# driverpower.net
KiCad netlist of a schematic drawn in Altium Designer
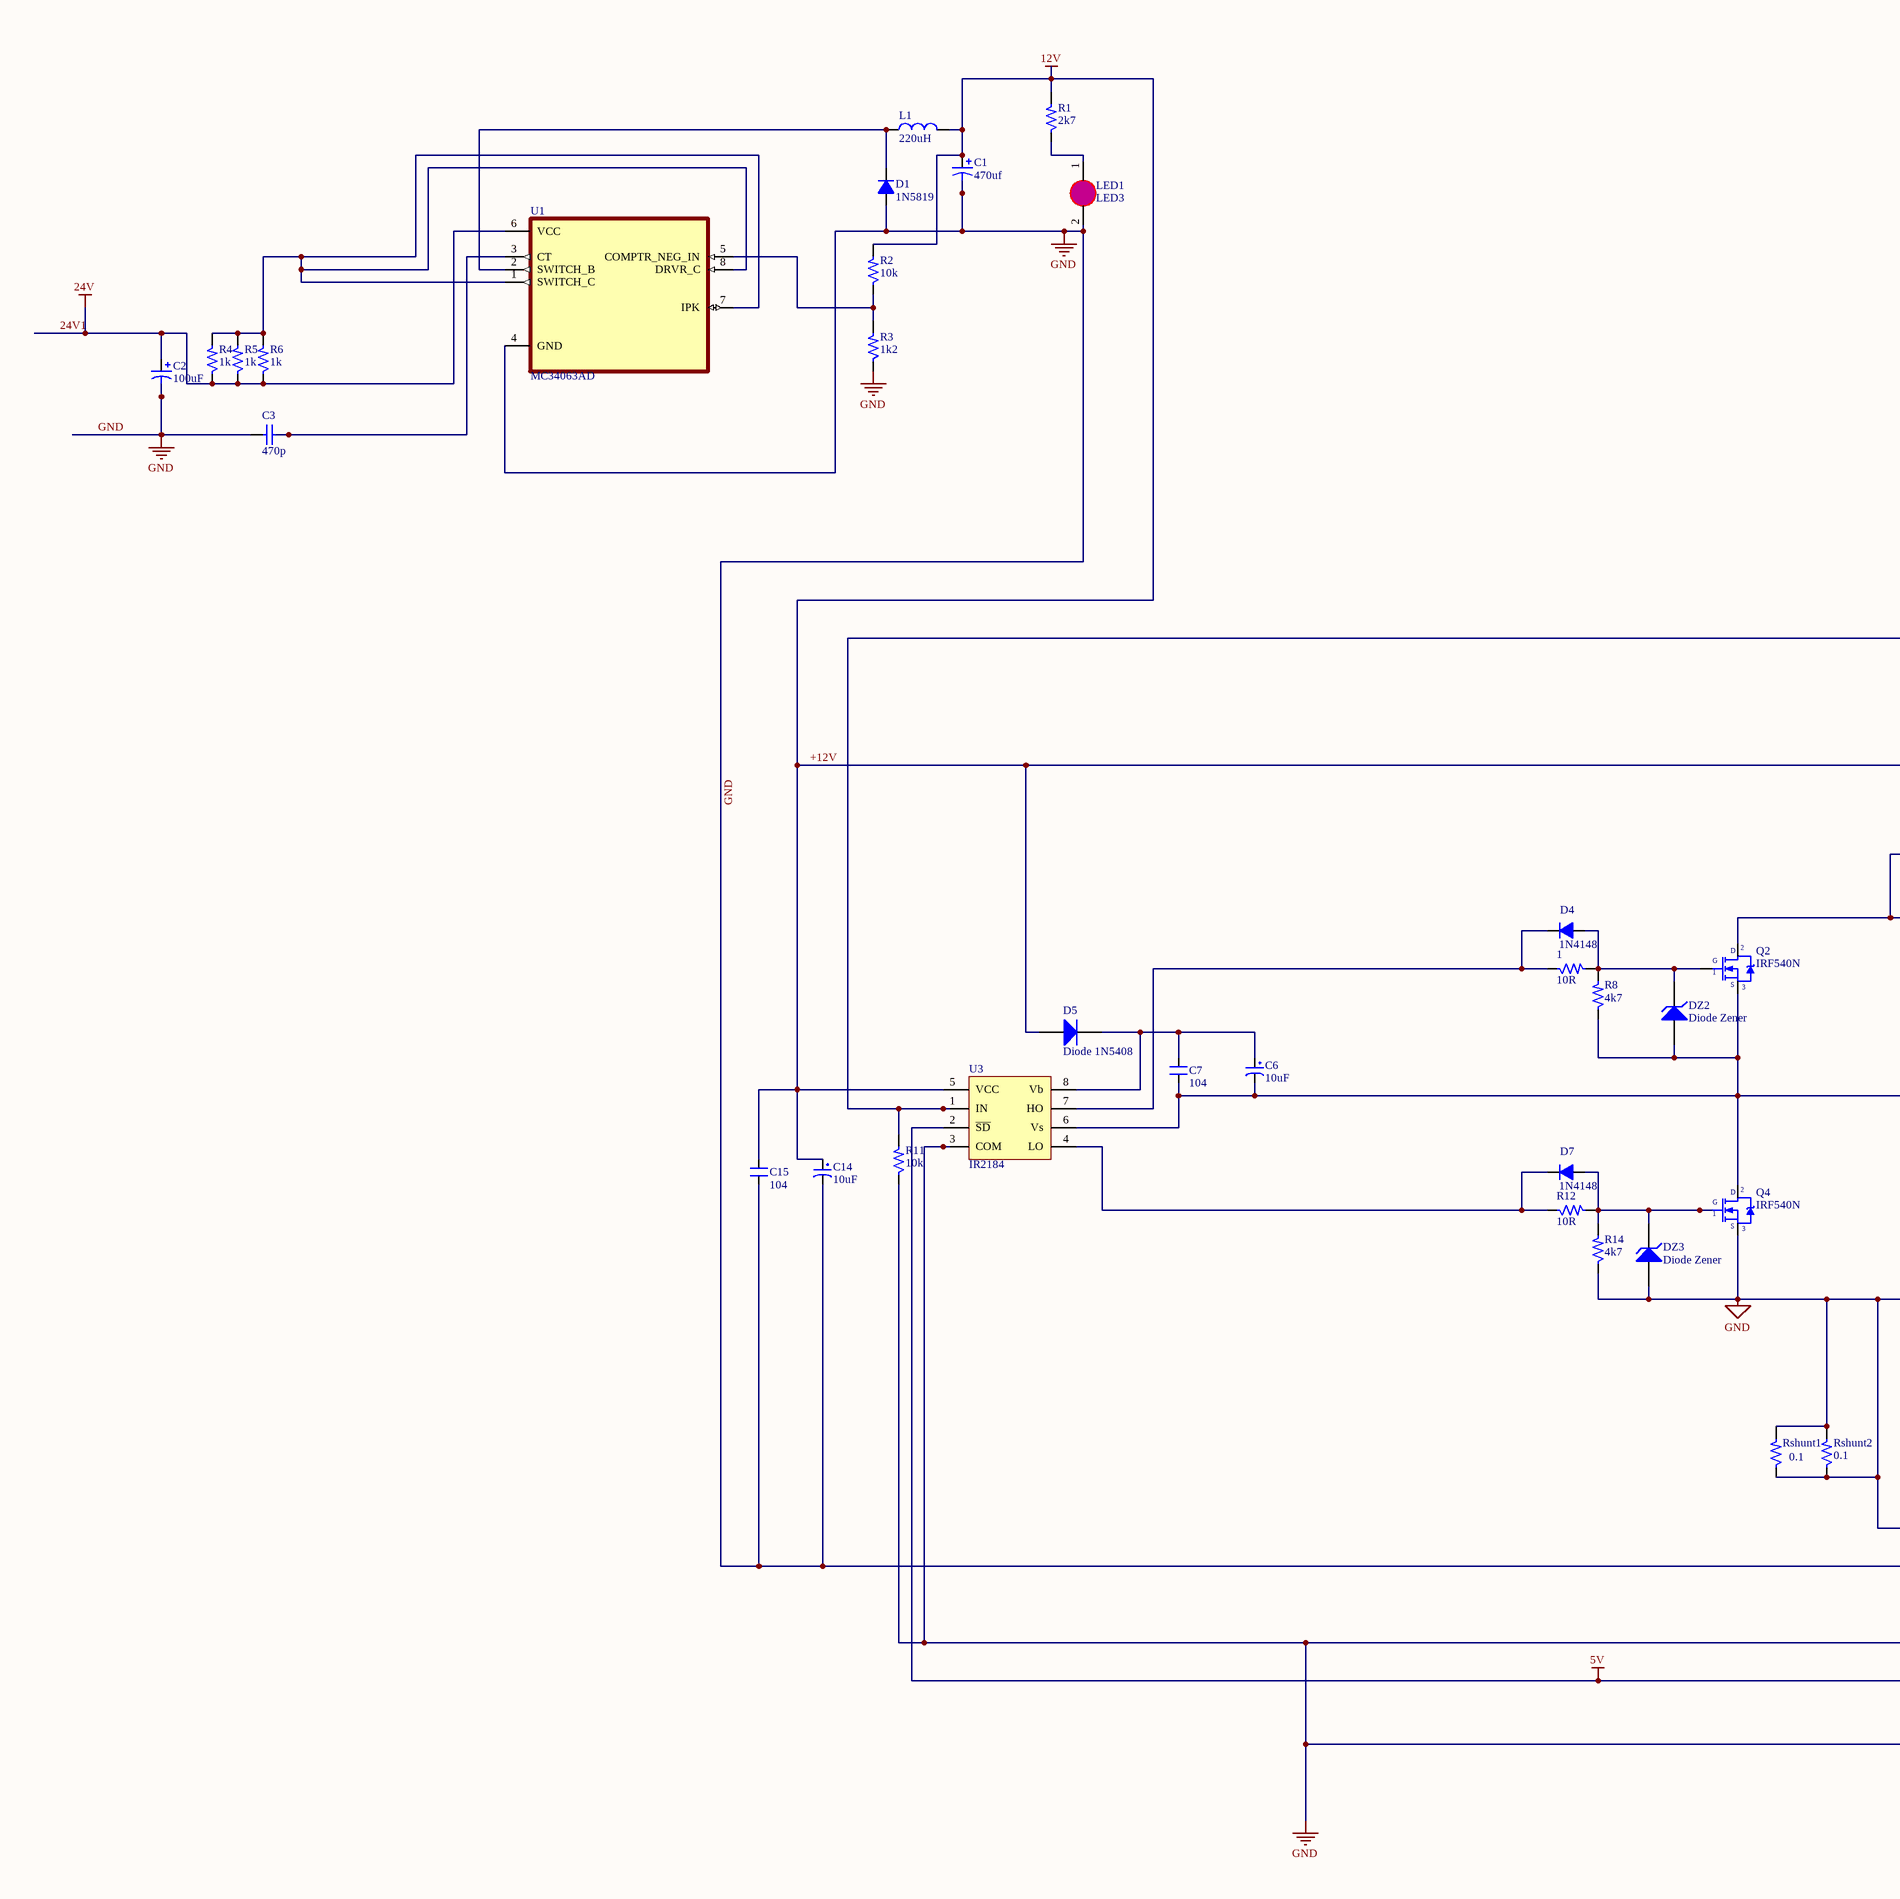
[diagram p0: driverpower.SchDoc, left]
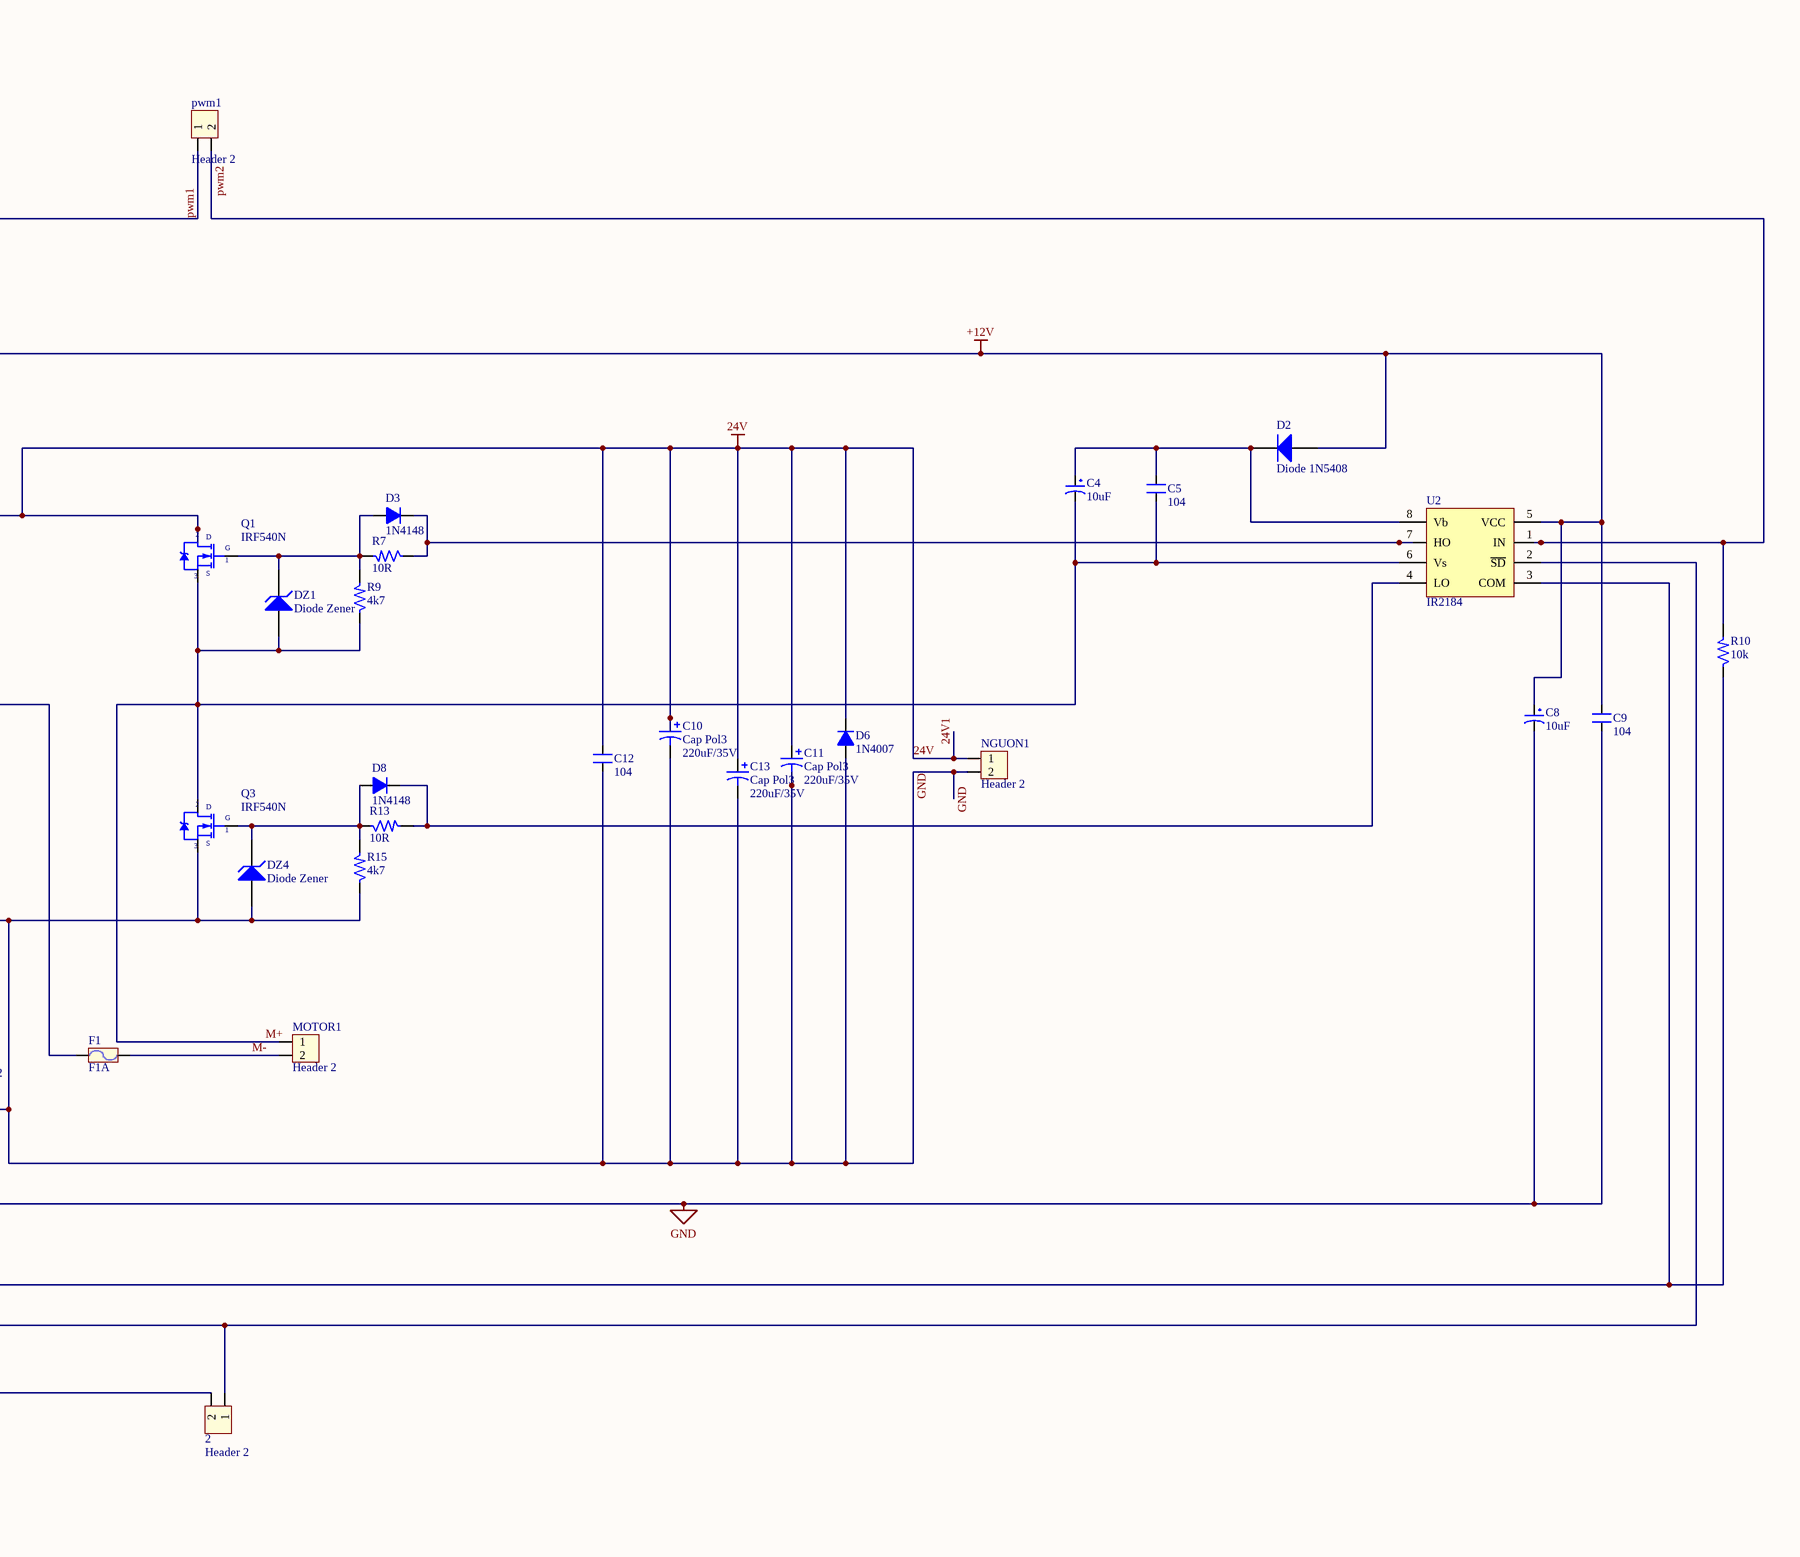
[diagram p1: driverpower.SchDoc, right]

(export (version "E")
  (design (tool "Eeschema 10.0.6"))
  (components
    (comp (ref "1")
      (value "10R")
      (footprint "SM-1206")
      (description "Resistor 1/4W")
      (libsource (lib "syhaunguyen") (part "R"))
    )
    (comp (ref "2")
      (value "Header 2")
      (footprint "HED2")
      (description "Header 2 (Green)")
      (libsource (lib "") (part "Hed2_1"))
    )
    (comp (ref "C1")
      (value "470uf")
      (footprint "C3MM")
      (description "Polarized Capacitor (Axial)")
      (fields (field (name "PUBLISHER") "Altium Limited"))
      (libsource (lib "Schematic") (part "Cap Pol 3mm"))
    )
    (comp (ref "C2")
      (value "100uF")
      (footprint "C3MM")
      (description "Polarized Capacitor (Axial)")
      (fields (field (name "PUBLISHER") "Altium Limited"))
      (libsource (lib "Schematic") (part "Cap Pol 3mm"))
    )
    (comp (ref "C3") (value "470p") (footprint "C1206") (libsource (lib "Schematic") (part "Cap SMD 1206")))
    (comp (ref "C4")
      (value "10uF")
      (footprint "CP1/2")
      (description "Cap P  0,1uF < 22uF , 16 - 50V")
      (libsource (lib "syhaunguyen") (part "CP1"))
    )
    (comp (ref "C5")
      (value "104")
      (footprint "SM-0805")
      (description "Cap SMD")
      (libsource (lib "My Library") (part "CM"))
    )
    (comp (ref "C6")
      (value "10uF")
      (footprint "CP1/2")
      (description "Cap P  0,1uF < 22uF , 16 - 50V")
      (libsource (lib "syhaunguyen") (part "CP1"))
    )
    (comp (ref "C7")
      (value "104")
      (footprint "SM-0805")
      (description "Cap SMD")
      (libsource (lib "My Library") (part "CM"))
    )
    (comp (ref "C8")
      (value "10uF")
      (footprint "CP1/2")
      (description "Cap P  0,1uF < 22uF , 16 - 50V")
      (libsource (lib "syhaunguyen") (part "CP1"))
    )
    (comp (ref "C9")
      (value "104")
      (footprint "SM-0805")
      (description "Cap SMD")
      (libsource (lib "My Library") (part "CM"))
    )
    (comp (ref "C10")
      (value "Cap Pol3")
      (footprint "CP2/5")
      (description "Polarized Capacitor (Surface Mount)")
      (fields (field (name "ALTIUM_VALUE") "220uF/35V") (field (name "PUBLISHER") "Altium Limited"))
      (libsource (lib "syhaunguyen") (part "Cap Pol3"))
    )
    (comp (ref "C11")
      (value "Cap Pol3")
      (footprint "CP2/5")
      (description "Polarized Capacitor (Surface Mount)")
      (fields (field (name "ALTIUM_VALUE") "220uF/35V") (field (name "PUBLISHER") "Altium Limited"))
      (libsource (lib "syhaunguyen") (part "Cap Pol3"))
    )
    (comp (ref "C12")
      (value "104")
      (footprint "SM-0805")
      (description "Cap SMD")
      (libsource (lib "My Library") (part "CM"))
    )
    (comp (ref "C13")
      (value "Cap Pol3")
      (footprint "CP2/5")
      (description "Polarized Capacitor (Surface Mount)")
      (fields (field (name "ALTIUM_VALUE") "220uF/35V") (field (name "PUBLISHER") "Altium Limited"))
      (libsource (lib "syhaunguyen") (part "Cap Pol3"))
    )
    (comp (ref "C14")
      (value "10uF")
      (footprint "CP1/2")
      (description "Cap P  0,1uF < 22uF , 16 - 50V")
      (libsource (lib "syhaunguyen") (part "CP1"))
    )
    (comp (ref "C15")
      (value "104")
      (footprint "SM-0805")
      (description "Cap SMD")
      (libsource (lib "My Library") (part "CM"))
    )
    (comp (ref "D1")
      (value "1N5819")
      (footprint "D5A")
      (description "Diode 5A")
      (libsource (lib "syhaunguyen") (part "D5A"))
    )
    (comp (ref "D2")
      (value "Diode 1N5408")
      (footprint "DO-201AD")
      (description "3 Amp Medium Power Silicon Rectifier Diode")
      (fields (field (name "PUBLISHER") "Altium Limited"))
      (libsource (lib "Miscellaneous Devices") (part "Diode 1N5408"))
    )
    (comp (ref "D3")
      (value "1N4148")
      (footprint "D1A")
      (description "Diode 1A")
      (libsource (lib "syhaunguyen") (part "D1A"))
    )
    (comp (ref "D4")
      (value "1N4148")
      (footprint "D1A")
      (description "Diode 1A")
      (libsource (lib "syhaunguyen") (part "D1A"))
    )
    (comp (ref "D5")
      (value "Diode 1N5408")
      (footprint "DO-201AD")
      (description "3 Amp Medium Power Silicon Rectifier Diode")
      (fields (field (name "PUBLISHER") "Altium Limited"))
      (libsource (lib "Miscellaneous Devices") (part "Diode 1N5408"))
    )
    (comp (ref "D6")
      (value "1N4007")
      (footprint "D1A")
      (description "Diode 1A")
      (libsource (lib "My Library") (part "D1A"))
    )
    (comp (ref "D7")
      (value "1N4148")
      (footprint "D1A")
      (description "Diode 1A")
      (libsource (lib "syhaunguyen") (part "D1A"))
    )
    (comp (ref "D8")
      (value "1N4148")
      (footprint "D1A")
      (description "Diode 1A")
      (libsource (lib "syhaunguyen") (part "D1A"))
    )
    (comp (ref "DZ1")
      (value "Diode Zener")
      (footprint "DIODE/NOM/0.5A")
      (description "Zener Diode")
      (fields (field (name "PUBLISHER") "Altium Limited"))
      (libsource (lib "Schematic") (part "Diode Zener"))
    )
    (comp (ref "DZ2")
      (value "Diode Zener")
      (footprint "DIODE/NOM/0.5A")
      (description "Zener Diode")
      (fields (field (name "PUBLISHER") "Altium Limited"))
      (libsource (lib "Schematic") (part "Diode Zener"))
    )
    (comp (ref "DZ3")
      (value "Diode Zener")
      (footprint "DIODE/NOM/0.5A")
      (description "Zener Diode")
      (fields (field (name "PUBLISHER") "Altium Limited"))
      (libsource (lib "Schematic") (part "Diode Zener"))
    )
    (comp (ref "DZ4")
      (value "Diode Zener")
      (footprint "DIODE/NOM/0.5A")
      (description "Zener Diode")
      (fields (field (name "PUBLISHER") "Altium Limited"))
      (libsource (lib "Schematic") (part "Diode Zener"))
    )
    (comp (ref "F1")
      (value "F1A")
      (footprint "Fuse")
      (description "Fuse")
      (fields (field (name "DESIGNED BY") "VanDungEvn"))
      (libsource (lib "syhaunguyen") (part "Fuse"))
    )
    (comp (ref "L1")
      (value "220uH")
      (footprint "L/0.4")
      (description "Inductor")
      (libsource (lib "syhaunguyen") (part "L1"))
    )
    (comp (ref "LED1")
      (value "LED3")
      (footprint "LED0805")
      (description "LED 3mm")
      (libsource (lib "Schematic") (part "LEDSMD"))
    )
    (comp (ref "MOTOR1")
      (value "Header 2")
      (footprint "HED2")
      (description "Header 2 (Green)")
      (libsource (lib "My Library") (part "Hed2"))
    )
    (comp (ref "NGUON1")
      (value "Header 2")
      (footprint "HED2")
      (description "Header 2 (Green)")
      (libsource (lib "My Library") (part "Hed2"))
    )
    (comp (ref "pwm1")
      (value "Header 2")
      (footprint "HED2")
      (description "Header 2 (Green)")
      (libsource (lib "syhaunguyen") (part "Hed2"))
    )
    (comp (ref "Q1")
      (value "IRF540N")
      (footprint "QTO-220")
      (description "MOSFET N - CHANNEL 500V - 0.75 - 8A - TO-220")
      (libsource (lib "syhaunguyen") (part "IRF840"))
    )
    (comp (ref "Q2")
      (value "IRF540N")
      (footprint "QTO-220")
      (description "MOSFET N - CHANNEL 500V - 0.75 - 8A - TO-220")
      (libsource (lib "syhaunguyen") (part "IRF840"))
    )
    (comp (ref "Q3")
      (value "IRF540N")
      (footprint "QTO-220")
      (description "MOSFET N - CHANNEL 500V - 0.75 - 8A - TO-220")
      (libsource (lib "syhaunguyen") (part "IRF840"))
    )
    (comp (ref "Q4")
      (value "IRF540N")
      (footprint "QTO-220")
      (description "MOSFET N - CHANNEL 500V - 0.75 - 8A - TO-220")
      (libsource (lib "syhaunguyen") (part "IRF840"))
    )
    (comp (ref "R1")
      (value "2k7")
      (footprint "SM-1206")
      (description "Resistor 1/4W")
      (libsource (lib "syhaunguyen") (part "R"))
    )
    (comp (ref "R2")
      (value "10k")
      (footprint "SM-1206")
      (description "Resistor 1/4W")
      (libsource (lib "syhaunguyen") (part "R"))
    )
    (comp (ref "R3")
      (value "1k2")
      (footprint "SM-1206")
      (description "Resistor 1/4W")
      (libsource (lib "syhaunguyen") (part "R"))
    )
    (comp (ref "R4")
      (value "1k")
      (footprint "SM-1206")
      (description "Resistor 1/4W")
      (libsource (lib "syhaunguyen") (part "R"))
    )
    (comp (ref "R5")
      (value "1k")
      (footprint "SM-1206")
      (description "Resistor 1/4W")
      (libsource (lib "syhaunguyen") (part "R"))
    )
    (comp (ref "R6")
      (value "1k")
      (footprint "SM-1206")
      (description "Resistor 1/4W")
      (libsource (lib "syhaunguyen") (part "R"))
    )
    (comp (ref "R7")
      (value "10R")
      (footprint "SM-1206")
      (description "Resistor 1/4W")
      (libsource (lib "syhaunguyen") (part "R"))
    )
    (comp (ref "R8")
      (value "4k7")
      (footprint "SM-1206")
      (description "Resistor 1/4W")
      (libsource (lib "syhaunguyen") (part "R"))
    )
    (comp (ref "R9")
      (value "4k7")
      (footprint "SM-1206")
      (description "Resistor 1/4W")
      (libsource (lib "syhaunguyen") (part "R"))
    )
    (comp (ref "R10")
      (value "10k")
      (footprint "SM-1206")
      (description "Resistor 1/4W")
      (libsource (lib "syhaunguyen") (part "R"))
    )
    (comp (ref "R11")
      (value "10k")
      (footprint "SM-1206")
      (description "Resistor 1/4W")
      (libsource (lib "syhaunguyen") (part "R"))
    )
    (comp (ref "R12")
      (value "10R")
      (footprint "SM-1206")
      (description "Resistor 1/4W")
      (libsource (lib "syhaunguyen") (part "R"))
    )
    (comp (ref "R13")
      (value "10R")
      (footprint "SM-1206")
      (description "Resistor 1/4W")
      (libsource (lib "syhaunguyen") (part "R"))
    )
    (comp (ref "R14")
      (value "4k7")
      (footprint "SM-1206")
      (description "Resistor 1/4W")
      (libsource (lib "syhaunguyen") (part "R"))
    )
    (comp (ref "R15")
      (value "4k7")
      (footprint "SM-1206")
      (description "Resistor 1/4W")
      (libsource (lib "syhaunguyen") (part "R"))
    )
    (comp (ref "Rshunt1")
      (value "0.1")
      (footprint "SM-1206")
      (description "Resistor 1/4W")
      (libsource (lib "syhaunguyen") (part "R"))
    )
    (comp (ref "Rshunt2")
      (value "0.1")
      (footprint "SM-1206")
      (description "Resistor 1/4W")
      (libsource (lib "syhaunguyen") (part "R"))
    )
    (comp (ref "U1")
      (value "MC34063AD")
      (footprint "SOIC127P599X175-8N")
      (fields (field (name "MF") "ON Semiconductor"))
      (libsource (lib "MC34063AD") (part "MC34063AD"))
    )
    (comp (ref "U2")
      (value "IR2184")
      (footprint "SOIC127P490X600X175-8N")
      (description "Half-Bridge Driver")
      (libsource (lib "syhaunguyen") (part "IR2184"))
    )
    (comp (ref "U3")
      (value "IR2184")
      (footprint "SOIC127P490X600X175-8N")
      (description "Half-Bridge Driver")
      (libsource (lib "") (part "IR2184_1"))
    )
  )
  (nets
    (net (code "1") (name "+12V") (class "Default")
      (node (ref "C1") (pin "1") (pinfunction "1_1") (pintype "passive"))
      (node (ref "C14") (pin "1") (pinfunction "1_1") (pintype "passive"))
      (node (ref "C15") (pin "2") (pinfunction "2_2") (pintype "passive"))
      (node (ref "C8") (pin "1") (pinfunction "1_1") (pintype "passive"))
      (node (ref "C9") (pin "2") (pinfunction "2_2") (pintype "passive"))
      (node (ref "D2") (pin "1") (pinfunction "A_1") (pintype "passive"))
      (node (ref "D5") (pin "1") (pinfunction "A_1") (pintype "passive"))
      (node (ref "L1") (pin "2") (pinfunction "2_2") (pintype "passive"))
      (node (ref "R1") (pin "2") (pinfunction "2_2") (pintype "passive"))
      (node (ref "R2") (pin "2") (pinfunction "2_2") (pintype "passive"))
      (node (ref "U2") (pin "5") (pinfunction "VCC_5") (pintype "passive"))
      (node (ref "U3") (pin "5") (pinfunction "VCC_5") (pintype "passive"))
    )
    (net (code "2") (name "/M+") (class "Default")
      (node (ref "C4") (pin "2") (pinfunction "2_2") (pintype "passive"))
      (node (ref "C5") (pin "1") (pinfunction "1_1") (pintype "passive"))
      (node (ref "DZ1") (pin "1") (pinfunction "A_1") (pintype "passive"))
      (node (ref "MOTOR1") (pin "1") (pinfunction "1_1") (pintype "passive"))
      (node (ref "Q1") (pin "3") (pinfunction "S_3") (pintype "passive"))
      (node (ref "Q3") (pin "2") (pinfunction "D_2") (pintype "passive"))
      (node (ref "R9") (pin "1") (pinfunction "1_1") (pintype "passive"))
      (node (ref "U2") (pin "6") (pinfunction "Vs_6") (pintype "passive"))
    )
    (net (code "3") (name "/M-") (class "Default")
      (node (ref "F1") (pin "2") (pinfunction "2_2") (pintype "passive"))
      (node (ref "MOTOR1") (pin "2") (pinfunction "2_2") (pintype "passive"))
    )
    (net (code "4") (name "/pwm1") (class "Default")
      (node (ref "R11") (pin "2") (pinfunction "2_2") (pintype "passive"))
      (node (ref "U3") (pin "1") (pinfunction "IN_1") (pintype "passive"))
      (node (ref "pwm1") (pin "1") (pinfunction "1_1") (pintype "passive"))
    )
    (net (code "5") (name "/pwm2") (class "Default")
      (node (ref "R10") (pin "2") (pinfunction "2_2") (pintype "passive"))
      (node (ref "U2") (pin "1") (pinfunction "IN_1") (pintype "passive"))
      (node (ref "pwm1") (pin "2") (pinfunction "2_2") (pintype "passive"))
    )
    (net (code "6") (name "5V") (class "Default")
      (node (ref "2") (pin "1") (pinfunction "1_1") (pintype "passive"))
      (node (ref "U2") (pin "2") (pinfunction "~{SD}_2") (pintype "passive"))
      (node (ref "U3") (pin "2") (pinfunction "~{SD}_2") (pintype "passive"))
    )
    (net (code "7") (name "24V") (class "Default")
      (node (ref "C10") (pin "1") (pinfunction "1_1") (pintype "passive"))
      (node (ref "C11") (pin "1") (pinfunction "1_1") (pintype "passive"))
      (node (ref "C12") (pin "2") (pinfunction "2_2") (pintype "passive"))
      (node (ref "C13") (pin "1") (pinfunction "1_1") (pintype "passive"))
      (node (ref "C2") (pin "1") (pinfunction "1_1") (pintype "passive"))
      (node (ref "D6") (pin "2") (pinfunction "K_2") (pintype "passive"))
      (node (ref "NGUON1") (pin "1") (pinfunction "1_1") (pintype "passive"))
      (node (ref "Q1") (pin "2") (pinfunction "D_2") (pintype "passive"))
      (node (ref "Q2") (pin "2") (pinfunction "D_2") (pintype "passive"))
      (node (ref "R4") (pin "1") (pinfunction "1_1") (pintype "passive"))
      (node (ref "R5") (pin "1") (pinfunction "1_1") (pintype "passive"))
      (node (ref "R6") (pin "1") (pinfunction "1_1") (pintype "passive"))
      (node (ref "U1") (pin "6") (pinfunction "VCC_6") (pintype "power_in"))
    )
    (net (code "8") (name "GND") (class "Default")
      (node (ref "2") (pin "2") (pinfunction "2_2") (pintype "passive"))
      (node (ref "C1") (pin "2") (pinfunction "2_2") (pintype "passive"))
      (node (ref "C10") (pin "2") (pinfunction "2_2") (pintype "passive"))
      (node (ref "C11") (pin "2") (pinfunction "2_2") (pintype "passive"))
      (node (ref "C12") (pin "1") (pinfunction "1_1") (pintype "passive"))
      (node (ref "C13") (pin "2") (pinfunction "2_2") (pintype "passive"))
      (node (ref "C14") (pin "2") (pinfunction "2_2") (pintype "passive"))
      (node (ref "C15") (pin "1") (pinfunction "1_1") (pintype "passive"))
      (node (ref "C2") (pin "2") (pinfunction "2_2") (pintype "passive"))
      (node (ref "C3") (pin "1") (pinfunction "1_1") (pintype "passive"))
      (node (ref "C8") (pin "2") (pinfunction "2_2") (pintype "passive"))
      (node (ref "C9") (pin "1") (pinfunction "1_1") (pintype "passive"))
      (node (ref "D1") (pin "1") (pinfunction "A_1") (pintype "passive"))
      (node (ref "D6") (pin "1") (pinfunction "A_1") (pintype "passive"))
      (node (ref "DZ3") (pin "1") (pinfunction "A_1") (pintype "passive"))
      (node (ref "DZ4") (pin "1") (pinfunction "A_1") (pintype "passive"))
      (node (ref "LED1") (pin "2") (pinfunction "K_2") (pintype "passive"))
      (node (ref "NGUON1") (pin "2") (pinfunction "2_2") (pintype "passive"))
      (node (ref "Q3") (pin "3") (pinfunction "S_3") (pintype "passive"))
      (node (ref "Q4") (pin "3") (pinfunction "S_3") (pintype "passive"))
      (node (ref "R10") (pin "1") (pinfunction "1_1") (pintype "passive"))
      (node (ref "R11") (pin "1") (pinfunction "1_1") (pintype "passive"))
      (node (ref "R14") (pin "1") (pinfunction "1_1") (pintype "passive"))
      (node (ref "R15") (pin "1") (pinfunction "1_1") (pintype "passive"))
      (node (ref "R3") (pin "1") (pinfunction "1_1") (pintype "passive"))
      (node (ref "Rshunt1") (pin "1") (pinfunction "1_1") (pintype "passive"))
      (node (ref "Rshunt1") (pin "2") (pinfunction "2_2") (pintype "passive"))
      (node (ref "Rshunt2") (pin "1") (pinfunction "1_1") (pintype "passive"))
      (node (ref "Rshunt2") (pin "2") (pinfunction "2_2") (pintype "passive"))
      (node (ref "U1") (pin "4") (pinfunction "GND_4") (pintype "power_in"))
      (node (ref "U2") (pin "3") (pinfunction "COM_3") (pintype "passive"))
      (node (ref "U3") (pin "3") (pinfunction "COM_3") (pintype "passive"))
    )
    (net (code "9") (name "Net-(D1-K)") (class "Default")
      (node (ref "D1") (pin "2") (pinfunction "K_2") (pintype "passive"))
      (node (ref "L1") (pin "1") (pinfunction "1_1") (pintype "passive"))
      (node (ref "U1") (pin "2") (pinfunction "SWITCH_B_2") (pintype "output"))
    )
    (net (code "10") (name "Net-(D2-K)") (class "Default")
      (node (ref "C4") (pin "1") (pinfunction "1_1") (pintype "passive"))
      (node (ref "C5") (pin "2") (pinfunction "2_2") (pintype "passive"))
      (node (ref "D2") (pin "2") (pinfunction "K_2") (pintype "passive"))
      (node (ref "U2") (pin "8") (pinfunction "Vb_8") (pintype "passive"))
    )
    (net (code "11") (name "Net-(D3-A)") (class "Default")
      (node (ref "D3") (pin "1") (pinfunction "A_1") (pintype "passive"))
      (node (ref "DZ1") (pin "2") (pinfunction "K_2") (pintype "passive"))
      (node (ref "Q1") (pin "1") (pinfunction "G_1") (pintype "passive"))
      (node (ref "R7") (pin "2") (pinfunction "2_2") (pintype "passive"))
      (node (ref "R9") (pin "2") (pinfunction "2_2") (pintype "passive"))
    )
    (net (code "12") (name "Net-(D3-K)") (class "Default")
      (node (ref "D3") (pin "2") (pinfunction "K_2") (pintype "passive"))
      (node (ref "R7") (pin "1") (pinfunction "1_1") (pintype "passive"))
      (node (ref "U2") (pin "7") (pinfunction "HO_7") (pintype "passive"))
    )
    (net (code "13") (name "Net-(D4-A)") (class "Default")
      (node (ref "1") (pin "2") (pinfunction "2_2") (pintype "passive"))
      (node (ref "D4") (pin "1") (pinfunction "A_1") (pintype "passive"))
      (node (ref "DZ2") (pin "2") (pinfunction "K_2") (pintype "passive"))
      (node (ref "Q2") (pin "1") (pinfunction "G_1") (pintype "passive"))
      (node (ref "R8") (pin "2") (pinfunction "2_2") (pintype "passive"))
    )
    (net (code "14") (name "Net-(D4-K)") (class "Default")
      (node (ref "1") (pin "1") (pinfunction "1_1") (pintype "passive"))
      (node (ref "D4") (pin "2") (pinfunction "K_2") (pintype "passive"))
      (node (ref "U3") (pin "7") (pinfunction "HO_7") (pintype "passive"))
    )
    (net (code "15") (name "Net-(D5-K)") (class "Default")
      (node (ref "C6") (pin "1") (pinfunction "1_1") (pintype "passive"))
      (node (ref "C7") (pin "2") (pinfunction "2_2") (pintype "passive"))
      (node (ref "D5") (pin "2") (pinfunction "K_2") (pintype "passive"))
      (node (ref "U3") (pin "8") (pinfunction "Vb_8") (pintype "passive"))
    )
    (net (code "16") (name "Net-(D7-A)") (class "Default")
      (node (ref "D7") (pin "1") (pinfunction "A_1") (pintype "passive"))
      (node (ref "DZ3") (pin "2") (pinfunction "K_2") (pintype "passive"))
      (node (ref "Q4") (pin "1") (pinfunction "G_1") (pintype "passive"))
      (node (ref "R12") (pin "2") (pinfunction "2_2") (pintype "passive"))
      (node (ref "R14") (pin "2") (pinfunction "2_2") (pintype "passive"))
    )
    (net (code "17") (name "Net-(D7-K)") (class "Default")
      (node (ref "D7") (pin "2") (pinfunction "K_2") (pintype "passive"))
      (node (ref "R12") (pin "1") (pinfunction "1_1") (pintype "passive"))
      (node (ref "U3") (pin "4") (pinfunction "LO_4") (pintype "passive"))
    )
    (net (code "18") (name "Net-(D8-A)") (class "Default")
      (node (ref "D8") (pin "1") (pinfunction "A_1") (pintype "passive"))
      (node (ref "DZ4") (pin "2") (pinfunction "K_2") (pintype "passive"))
      (node (ref "Q3") (pin "1") (pinfunction "G_1") (pintype "passive"))
      (node (ref "R13") (pin "1") (pinfunction "1_1") (pintype "passive"))
      (node (ref "R15") (pin "2") (pinfunction "2_2") (pintype "passive"))
    )
    (net (code "19") (name "Net-(D8-K)") (class "Default")
      (node (ref "D8") (pin "2") (pinfunction "K_2") (pintype "passive"))
      (node (ref "R13") (pin "2") (pinfunction "2_2") (pintype "passive"))
      (node (ref "U2") (pin "4") (pinfunction "LO_4") (pintype "passive"))
    )
    (net (code "20") (name "Net-(DZ2-A)") (class "Default")
      (node (ref "C6") (pin "2") (pinfunction "2_2") (pintype "passive"))
      (node (ref "C7") (pin "1") (pinfunction "1_1") (pintype "passive"))
      (node (ref "DZ2") (pin "1") (pinfunction "A_1") (pintype "passive"))
      (node (ref "F1") (pin "1") (pinfunction "1_1") (pintype "passive"))
      (node (ref "Q2") (pin "3") (pinfunction "S_3") (pintype "passive"))
      (node (ref "Q4") (pin "2") (pinfunction "D_2") (pintype "passive"))
      (node (ref "R8") (pin "1") (pinfunction "1_1") (pintype "passive"))
      (node (ref "U3") (pin "6") (pinfunction "Vs_6") (pintype "passive"))
    )
    (net (code "21") (name "Net-(LED1-A)") (class "Default")
      (node (ref "LED1") (pin "1") (pinfunction "A_1") (pintype "passive"))
      (node (ref "R1") (pin "1") (pinfunction "1_1") (pintype "passive"))
    )
    (net (code "22") (name "Net-(U1-COMPTR_NEG_IN)") (class "Default")
      (node (ref "R2") (pin "1") (pinfunction "1_1") (pintype "passive"))
      (node (ref "R3") (pin "2") (pinfunction "2_2") (pintype "passive"))
      (node (ref "U1") (pin "5") (pinfunction "COMPTR_NEG_IN_5") (pintype "input"))
    )
    (net (code "23") (name "Net-(U1-CT)") (class "Default")
      (node (ref "C3") (pin "2") (pinfunction "2_2") (pintype "passive"))
      (node (ref "U1") (pin "3") (pinfunction "CT_3") (pintype "output"))
    )
    (net (code "24") (name "Net-(U1-DRVR_C)") (class "Default")
      (node (ref "R4") (pin "2") (pinfunction "2_2") (pintype "passive"))
      (node (ref "R5") (pin "2") (pinfunction "2_2") (pintype "passive"))
      (node (ref "R6") (pin "2") (pinfunction "2_2") (pintype "passive"))
      (node (ref "U1") (pin "1") (pinfunction "SWITCH_C_1") (pintype "output"))
      (node (ref "U1") (pin "7") (pinfunction "IPK_7") (pintype "bidirectional"))
      (node (ref "U1") (pin "8") (pinfunction "DRVR_C_8") (pintype "input"))
    )
  )
)
